# stm32f410rb_pcm5100.net
KiCad netlist of a schematic drawn in EAGLE
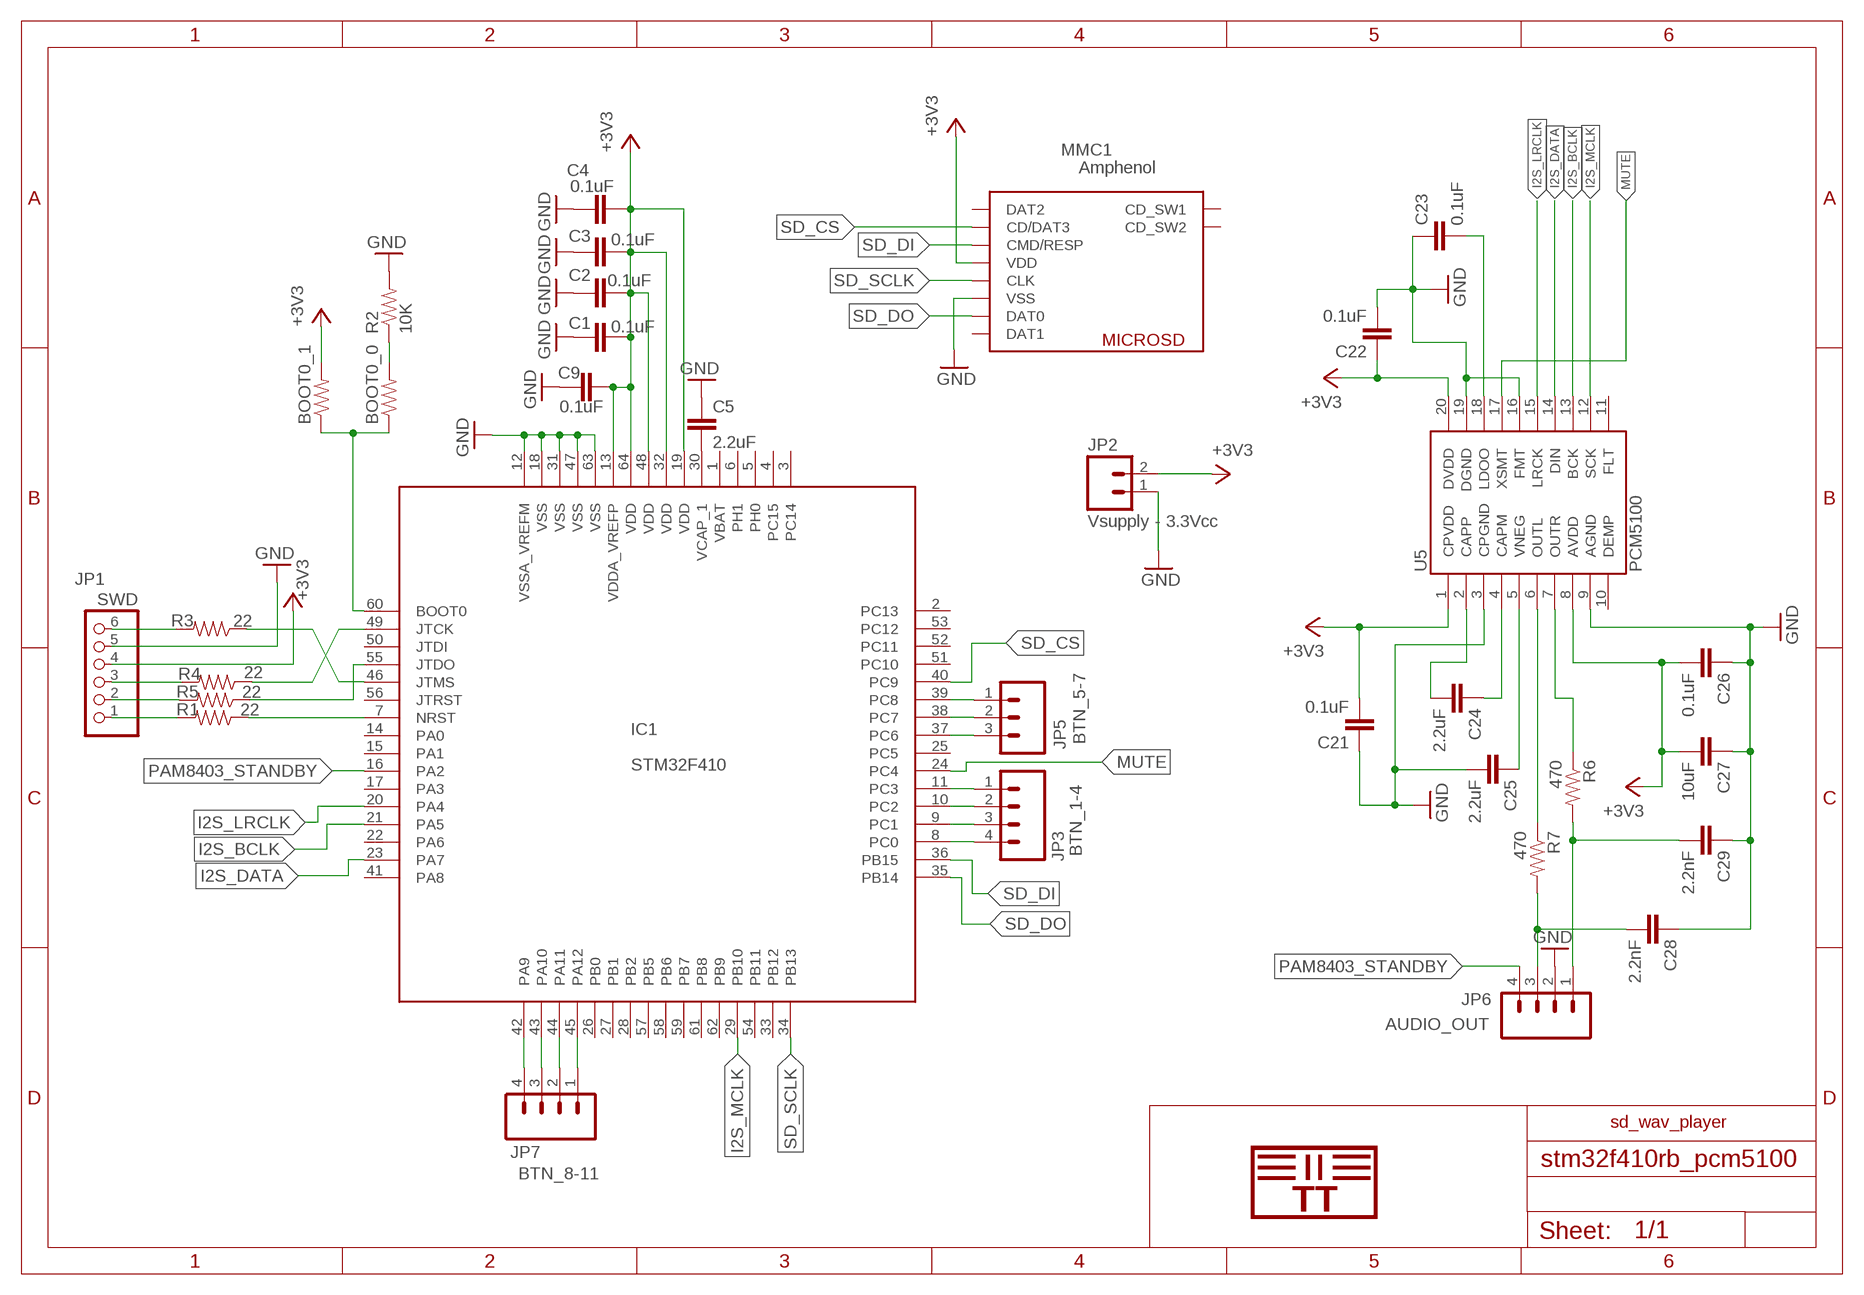
[diagram p0: schematic, sheet 1]

(export (version "E")
  (design (tool "Eeschema 10.0.6"))
  (components
    (comp (ref "BOOT0_0")
      (value "RESISTOR0603-RES")
      (footprint "eagle-import:0603-RES")
      (libsource (lib "eagle-import") (part "RESISTOR0603-RES"))
    )
    (comp (ref "BOOT0_1")
      (value "RESISTOR0603-RES")
      (footprint "eagle-import:0603-RES")
      (libsource (lib "eagle-import") (part "RESISTOR0603-RES"))
    )
    (comp (ref "C1")
      (value "0.1uF")
      (footprint "eagle-import:0805")
      (libsource (lib "eagle-import") (part "CAP0805"))
    )
    (comp (ref "C2")
      (value "0.1uF")
      (footprint "eagle-import:0805")
      (libsource (lib "eagle-import") (part "CAP0805"))
    )
    (comp (ref "C3")
      (value "0.1uF")
      (footprint "eagle-import:0805")
      (libsource (lib "eagle-import") (part "CAP0805"))
    )
    (comp (ref "C4")
      (value "0.1uF")
      (footprint "eagle-import:0805")
      (libsource (lib "eagle-import") (part "CAP0805"))
    )
    (comp (ref "C5")
      (value "2.2uF")
      (footprint "eagle-import:0805")
      (libsource (lib "eagle-import") (part "CAP0805"))
    )
    (comp (ref "C9")
      (value "0.1uF")
      (footprint "eagle-import:0805")
      (libsource (lib "eagle-import") (part "CAP0805"))
    )
    (comp (ref "C21")
      (value "0.1uF")
      (footprint "eagle-import:0805")
      (libsource (lib "eagle-import") (part "CAP0805"))
    )
    (comp (ref "C22")
      (value "0.1uF")
      (footprint "eagle-import:0805")
      (libsource (lib "eagle-import") (part "CAP0805"))
    )
    (comp (ref "C23")
      (value "0.1uF")
      (footprint "eagle-import:0805")
      (libsource (lib "eagle-import") (part "CAP0805"))
    )
    (comp (ref "C24")
      (value "2.2uF")
      (footprint "eagle-import:0805")
      (libsource (lib "eagle-import") (part "CAP0805"))
    )
    (comp (ref "C25")
      (value "2.2uF")
      (footprint "eagle-import:0805")
      (libsource (lib "eagle-import") (part "CAP0805"))
    )
    (comp (ref "C26")
      (value "0.1uF")
      (footprint "eagle-import:0805")
      (libsource (lib "eagle-import") (part "CAP0805"))
    )
    (comp (ref "C27")
      (value "10uF")
      (footprint "eagle-import:0805")
      (libsource (lib "eagle-import") (part "CAP0805"))
    )
    (comp (ref "C28")
      (value "2.2nF")
      (footprint "eagle-import:0805")
      (libsource (lib "eagle-import") (part "CAP0805"))
    )
    (comp (ref "C29")
      (value "2.2nF")
      (footprint "eagle-import:0805")
      (libsource (lib "eagle-import") (part "CAP0805"))
    )
    (comp (ref "IC1")
      (value "STM32F410")
      (footprint "eagle-import:LQFP64")
      (libsource (lib "eagle-import") (part "STM32F410_8_B_LQFP64"))
    )
    (comp (ref "JP1")
      (value "SWD")
      (footprint "eagle-import:1X06")
      (libsource (lib "eagle-import") (part "PINHD-1X6"))
    )
    (comp (ref "JP2")
      (value "Vsupply - 3.3Vcc")
      (footprint "eagle-import:SCREWTERMINAL-3.5MM-2")
      (libsource (lib "eagle-import") (part "M023.5MM"))
    )
    (comp (ref "JP3")
      (value "BTN_1-4")
      (footprint "eagle-import:SCREWTERMINAL-3.5MM-4")
      (libsource (lib "eagle-import") (part "M04SCREW"))
    )
    (comp (ref "JP5")
      (value "BTN_5-7")
      (footprint "eagle-import:SCREWTERMINAL-3.5MM-3")
      (libsource (lib "eagle-import") (part "M03SCREW"))
    )
    (comp (ref "JP6")
      (value "AUDIO_OUT")
      (footprint "eagle-import:SCREWTERMINAL-3.5MM-4")
      (libsource (lib "eagle-import") (part "M04SCREW"))
    )
    (comp (ref "JP7")
      (value "BTN_8-11")
      (footprint "eagle-import:SCREWTERMINAL-3.5MM-4")
      (libsource (lib "eagle-import") (part "M04SCREW"))
    )
    (comp (ref "MMC1")
      (value "Amphenol")
      (footprint "eagle-import:MICROSD_AMPHENOL")
      (libsource (lib "eagle-import") (part "MICROSD_AMPHENOL"))
    )
    (comp (ref "R1")
      (value "22")
      (footprint "eagle-import:0805")
      (libsource (lib "eagle-import") (part "RESISTOR0805-RES"))
    )
    (comp (ref "R2")
      (value "10K")
      (footprint "eagle-import:0805")
      (libsource (lib "eagle-import") (part "RESISTOR0805-RES"))
    )
    (comp (ref "R3")
      (value "22")
      (footprint "eagle-import:0805")
      (libsource (lib "eagle-import") (part "RESISTOR0805-RES"))
    )
    (comp (ref "R4")
      (value "22")
      (footprint "eagle-import:0805")
      (libsource (lib "eagle-import") (part "RESISTOR0805-RES"))
    )
    (comp (ref "R5")
      (value "22")
      (footprint "eagle-import:0805")
      (libsource (lib "eagle-import") (part "RESISTOR0805-RES"))
    )
    (comp (ref "R6")
      (value "470")
      (footprint "eagle-import:0805")
      (libsource (lib "eagle-import") (part "RESISTOR0805-RES"))
    )
    (comp (ref "R7")
      (value "470")
      (footprint "eagle-import:0805")
      (libsource (lib "eagle-import") (part "RESISTOR0805-RES"))
    )
    (comp (ref "U5")
      (value "PCM5100")
      (footprint "eagle-import:ROBERTSONICS_PW_R-PDSO-G20")
      (libsource (lib "eagle-import") (part "ROBERTSONICS_PCM5100"))
    )
  )
  (nets
    (net (code "1") (name "+3V3") (class "Default")
      (node (ref "BOOT0_1") (pin "2") (pinfunction "2_2") (pintype "passive"))
      (node (ref "C1") (pin "1") (pinfunction "1_1") (pintype "passive"))
      (node (ref "C2") (pin "1") (pinfunction "1_1") (pintype "passive"))
      (node (ref "C21") (pin "2") (pinfunction "2_2") (pintype "passive"))
      (node (ref "C22") (pin "1") (pinfunction "1_1") (pintype "passive"))
      (node (ref "C26") (pin "2") (pinfunction "2_2") (pintype "passive"))
      (node (ref "C27") (pin "2") (pinfunction "2_2") (pintype "passive"))
      (node (ref "C3") (pin "1") (pinfunction "1_1") (pintype "passive"))
      (node (ref "C4") (pin "1") (pinfunction "1_1") (pintype "passive"))
      (node (ref "C9") (pin "1") (pinfunction "1_1") (pintype "passive"))
      (node (ref "IC1") (pin "13") (pinfunction "VDDA_VREFP_13") (pintype "power_in"))
      (node (ref "IC1") (pin "19") (pinfunction "VDD_19") (pintype "power_in"))
      (node (ref "IC1") (pin "32") (pinfunction "VDD_32") (pintype "power_in"))
      (node (ref "IC1") (pin "48") (pinfunction "VDD_48") (pintype "power_in"))
      (node (ref "IC1") (pin "64") (pinfunction "VDD_64") (pintype "power_in"))
      (node (ref "JP1") (pin "4") (pinfunction "4_4") (pintype "passive"))
      (node (ref "JP2") (pin "2") (pinfunction "2_2") (pintype "passive"))
      (node (ref "MMC1") (pin "VDD") (pinfunction "VDD_VDD") (pintype "bidirectional"))
      (node (ref "U5") (pin "1") (pinfunction "CPVDD_1") (pintype "bidirectional"))
      (node (ref "U5") (pin "20") (pinfunction "DVDD_20") (pintype "bidirectional"))
      (node (ref "U5") (pin "8") (pinfunction "AVDD_8") (pintype "bidirectional"))
    )
    (net (code "2") (name "GND") (class "Default")
      (node (ref "C1") (pin "2") (pinfunction "2_2") (pintype "passive"))
      (node (ref "C2") (pin "2") (pinfunction "2_2") (pintype "passive"))
      (node (ref "C21") (pin "1") (pinfunction "1_1") (pintype "passive"))
      (node (ref "C22") (pin "2") (pinfunction "2_2") (pintype "passive"))
      (node (ref "C23") (pin "1") (pinfunction "1_1") (pintype "passive"))
      (node (ref "C25") (pin "2") (pinfunction "2_2") (pintype "passive"))
      (node (ref "C26") (pin "1") (pinfunction "1_1") (pintype "passive"))
      (node (ref "C27") (pin "1") (pinfunction "1_1") (pintype "passive"))
      (node (ref "C28") (pin "1") (pinfunction "1_1") (pintype "passive"))
      (node (ref "C29") (pin "1") (pinfunction "1_1") (pintype "passive"))
      (node (ref "C3") (pin "2") (pinfunction "2_2") (pintype "passive"))
      (node (ref "C4") (pin "2") (pinfunction "2_2") (pintype "passive"))
      (node (ref "C5") (pin "1") (pinfunction "1_1") (pintype "passive"))
      (node (ref "C9") (pin "2") (pinfunction "2_2") (pintype "passive"))
      (node (ref "IC1") (pin "12") (pinfunction "VSSA_VREFM_12") (pintype "power_in"))
      (node (ref "IC1") (pin "18") (pinfunction "VSS_18") (pintype "power_in"))
      (node (ref "IC1") (pin "31") (pinfunction "VSS_31") (pintype "power_in"))
      (node (ref "IC1") (pin "47") (pinfunction "VSS_47") (pintype "power_in"))
      (node (ref "IC1") (pin "63") (pinfunction "VSS_63") (pintype "power_in"))
      (node (ref "JP1") (pin "5") (pinfunction "5_5") (pintype "passive"))
      (node (ref "JP2") (pin "1") (pinfunction "1_1") (pintype "passive"))
      (node (ref "JP6") (pin "2") (pinfunction "2_2") (pintype "passive"))
      (node (ref "MMC1") (pin "VSS") (pinfunction "VSS_VSS") (pintype "bidirectional"))
      (node (ref "R2") (pin "2") (pinfunction "2_2") (pintype "passive"))
      (node (ref "U5") (pin "16") (pinfunction "FMT_16") (pintype "bidirectional"))
      (node (ref "U5") (pin "19") (pinfunction "DGND_19") (pintype "bidirectional"))
      (node (ref "U5") (pin "3") (pinfunction "CPGND_3") (pintype "bidirectional"))
      (node (ref "U5") (pin "9") (pinfunction "AGND_9") (pintype "bidirectional"))
    )
    (net (code "3") (name "I2S_BCLK") (class "Default")
      (node (ref "IC1") (pin "21") (pinfunction "PA5_21") (pintype "bidirectional"))
      (node (ref "U5") (pin "13") (pinfunction "BCK_13") (pintype "bidirectional"))
    )
    (net (code "4") (name "I2S_DATA") (class "Default")
      (node (ref "IC1") (pin "23") (pinfunction "PA7_23") (pintype "bidirectional"))
      (node (ref "U5") (pin "14") (pinfunction "DIN_14") (pintype "bidirectional"))
    )
    (net (code "5") (name "I2S_LRCLK") (class "Default")
      (node (ref "IC1") (pin "20") (pinfunction "PA4_20") (pintype "bidirectional"))
      (node (ref "U5") (pin "15") (pinfunction "LRCK_15") (pintype "bidirectional"))
    )
    (net (code "6") (name "I2S_MCLK") (class "Default")
      (node (ref "IC1") (pin "29") (pinfunction "PB10_29") (pintype "bidirectional"))
      (node (ref "U5") (pin "12") (pinfunction "SCK_12") (pintype "bidirectional"))
    )
    (net (code "7") (name "MUTE") (class "Default")
      (node (ref "IC1") (pin "24") (pinfunction "PC4_24") (pintype "bidirectional"))
      (node (ref "U5") (pin "17") (pinfunction "XSMT_17") (pintype "bidirectional"))
    )
    (net (code "8") (name "Net-(BOOT0_0-Pad2)") (class "Default")
      (node (ref "BOOT0_0") (pin "2") (pinfunction "2_2") (pintype "passive"))
      (node (ref "R2") (pin "1") (pinfunction "1_1") (pintype "passive"))
    )
    (net (code "9") (name "Net-(C28-Pad2)") (class "Default")
      (node (ref "C28") (pin "2") (pinfunction "2_2") (pintype "passive"))
      (node (ref "JP6") (pin "3") (pinfunction "3_3") (pintype "passive"))
      (node (ref "R7") (pin "2") (pinfunction "2_2") (pintype "passive"))
    )
    (net (code "10") (name "Net-(C29-Pad2)") (class "Default")
      (node (ref "C29") (pin "2") (pinfunction "2_2") (pintype "passive"))
      (node (ref "JP6") (pin "1") (pinfunction "1_1") (pintype "passive"))
      (node (ref "R6") (pin "2") (pinfunction "2_2") (pintype "passive"))
    )
    (net (code "11") (name "Net-(IC1-BOOT0)") (class "Default")
      (node (ref "BOOT0_0") (pin "1") (pinfunction "1_1") (pintype "passive"))
      (node (ref "BOOT0_1") (pin "1") (pinfunction "1_1") (pintype "passive"))
      (node (ref "IC1") (pin "60") (pinfunction "BOOT0_60") (pintype "input"))
    )
    (net (code "12") (name "Net-(IC1-JTCK)") (class "Default")
      (node (ref "IC1") (pin "49") (pinfunction "JTCK_49") (pintype "input"))
      (node (ref "R4") (pin "1") (pinfunction "1_1") (pintype "passive"))
    )
    (net (code "13") (name "Net-(IC1-JTDO)") (class "Default")
      (node (ref "IC1") (pin "55") (pinfunction "JTDO_55") (pintype "output"))
      (node (ref "R5") (pin "1") (pinfunction "1_1") (pintype "passive"))
    )
    (net (code "14") (name "Net-(IC1-JTMS)") (class "Default")
      (node (ref "IC1") (pin "46") (pinfunction "JTMS_46") (pintype "input"))
      (node (ref "R3") (pin "1") (pinfunction "1_1") (pintype "passive"))
    )
    (net (code "15") (name "Net-(IC1-NRST)") (class "Default")
      (node (ref "IC1") (pin "7") (pinfunction "NRST_7") (pintype "input"))
      (node (ref "R1") (pin "1") (pinfunction "1_1") (pintype "passive"))
    )
    (net (code "16") (name "Net-(IC1-PA9)") (class "Default")
      (node (ref "IC1") (pin "42") (pinfunction "PA9_42") (pintype "bidirectional"))
      (node (ref "JP7") (pin "4") (pinfunction "4_4") (pintype "passive"))
    )
    (net (code "17") (name "Net-(IC1-PA10)") (class "Default")
      (node (ref "IC1") (pin "43") (pinfunction "PA10_43") (pintype "bidirectional"))
      (node (ref "JP7") (pin "3") (pinfunction "3_3") (pintype "passive"))
    )
    (net (code "18") (name "Net-(IC1-PA11)") (class "Default")
      (node (ref "IC1") (pin "44") (pinfunction "PA11_44") (pintype "bidirectional"))
      (node (ref "JP7") (pin "2") (pinfunction "2_2") (pintype "passive"))
    )
    (net (code "19") (name "Net-(IC1-PA12)") (class "Default")
      (node (ref "IC1") (pin "45") (pinfunction "PA12_45") (pintype "bidirectional"))
      (node (ref "JP7") (pin "1") (pinfunction "1_1") (pintype "passive"))
    )
    (net (code "20") (name "Net-(IC1-PC0)") (class "Default")
      (node (ref "IC1") (pin "8") (pinfunction "PC0_8") (pintype "bidirectional"))
      (node (ref "JP3") (pin "4") (pinfunction "4_4") (pintype "passive"))
    )
    (net (code "21") (name "Net-(IC1-PC1)") (class "Default")
      (node (ref "IC1") (pin "9") (pinfunction "PC1_9") (pintype "bidirectional"))
      (node (ref "JP3") (pin "3") (pinfunction "3_3") (pintype "passive"))
    )
    (net (code "22") (name "Net-(IC1-PC2)") (class "Default")
      (node (ref "IC1") (pin "10") (pinfunction "PC2_10") (pintype "bidirectional"))
      (node (ref "JP3") (pin "2") (pinfunction "2_2") (pintype "passive"))
    )
    (net (code "23") (name "Net-(IC1-PC3)") (class "Default")
      (node (ref "IC1") (pin "11") (pinfunction "PC3_11") (pintype "bidirectional"))
      (node (ref "JP3") (pin "1") (pinfunction "1_1") (pintype "passive"))
    )
    (net (code "24") (name "Net-(IC1-PC6)") (class "Default")
      (node (ref "IC1") (pin "37") (pinfunction "PC6_37") (pintype "bidirectional"))
      (node (ref "JP5") (pin "3") (pinfunction "3_3") (pintype "passive"))
    )
    (net (code "25") (name "Net-(IC1-PC7)") (class "Default")
      (node (ref "IC1") (pin "38") (pinfunction "PC7_38") (pintype "bidirectional"))
      (node (ref "JP5") (pin "2") (pinfunction "2_2") (pintype "passive"))
    )
    (net (code "26") (name "Net-(IC1-PC8)") (class "Default")
      (node (ref "IC1") (pin "39") (pinfunction "PC8_39") (pintype "bidirectional"))
      (node (ref "JP5") (pin "1") (pinfunction "1_1") (pintype "passive"))
    )
    (net (code "27") (name "Net-(IC1-VCAP_1)") (class "Default")
      (node (ref "C5") (pin "2") (pinfunction "2_2") (pintype "passive"))
      (node (ref "IC1") (pin "30") (pinfunction "VCAP_1_30") (pintype "passive"))
    )
    (net (code "28") (name "Net-(JP1-Pad1)") (class "Default")
      (node (ref "JP1") (pin "1") (pinfunction "1_1") (pintype "passive"))
      (node (ref "R1") (pin "2") (pinfunction "2_2") (pintype "passive"))
    )
    (net (code "29") (name "Net-(JP1-Pad2)") (class "Default")
      (node (ref "JP1") (pin "2") (pinfunction "2_2") (pintype "passive"))
      (node (ref "R5") (pin "2") (pinfunction "2_2") (pintype "passive"))
    )
    (net (code "30") (name "Net-(JP1-Pad3)") (class "Default")
      (node (ref "JP1") (pin "3") (pinfunction "3_3") (pintype "passive"))
      (node (ref "R4") (pin "2") (pinfunction "2_2") (pintype "passive"))
    )
    (net (code "31") (name "Net-(JP1-Pad6)") (class "Default")
      (node (ref "JP1") (pin "6") (pinfunction "6_6") (pintype "passive"))
      (node (ref "R3") (pin "2") (pinfunction "2_2") (pintype "passive"))
    )
    (net (code "32") (name "Net-(U5-CAPM)") (class "Default")
      (node (ref "C24") (pin "1") (pinfunction "1_1") (pintype "passive"))
      (node (ref "U5") (pin "4") (pinfunction "CAPM_4") (pintype "bidirectional"))
    )
    (net (code "33") (name "Net-(U5-CAPP)") (class "Default")
      (node (ref "C24") (pin "2") (pinfunction "2_2") (pintype "passive"))
      (node (ref "U5") (pin "2") (pinfunction "CAPP_2") (pintype "bidirectional"))
    )
    (net (code "34") (name "Net-(U5-LDOO)") (class "Default")
      (node (ref "C23") (pin "2") (pinfunction "2_2") (pintype "passive"))
      (node (ref "U5") (pin "18") (pinfunction "LDOO_18") (pintype "bidirectional"))
    )
    (net (code "35") (name "Net-(U5-OUTL)") (class "Default")
      (node (ref "R7") (pin "1") (pinfunction "1_1") (pintype "passive"))
      (node (ref "U5") (pin "6") (pinfunction "OUTL_6") (pintype "bidirectional"))
    )
    (net (code "36") (name "Net-(U5-OUTR)") (class "Default")
      (node (ref "R6") (pin "1") (pinfunction "1_1") (pintype "passive"))
      (node (ref "U5") (pin "7") (pinfunction "OUTR_7") (pintype "bidirectional"))
    )
    (net (code "37") (name "Net-(U5-VNEG)") (class "Default")
      (node (ref "C25") (pin "1") (pinfunction "1_1") (pintype "passive"))
      (node (ref "U5") (pin "5") (pinfunction "VNEG_5") (pintype "bidirectional"))
    )
    (net (code "38") (name "PAM8403_STANDBY") (class "Default")
      (node (ref "IC1") (pin "16") (pinfunction "PA2_16") (pintype "bidirectional"))
      (node (ref "JP6") (pin "4") (pinfunction "4_4") (pintype "passive"))
    )
    (net (code "39") (name "SD_CS") (class "Default")
      (node (ref "IC1") (pin "40") (pinfunction "PC9_40") (pintype "bidirectional"))
      (node (ref "MMC1") (pin "CD/DAT3") (pinfunction "CD/DAT3_CD/DAT3") (pintype "bidirectional"))
    )
    (net (code "40") (name "SD_DI") (class "Default")
      (node (ref "IC1") (pin "36") (pinfunction "PB15_36") (pintype "bidirectional"))
      (node (ref "MMC1") (pin "CMD/RESP") (pinfunction "CMD/RESP_CMD/RESP") (pintype "bidirectional"))
    )
    (net (code "41") (name "SD_DO") (class "Default")
      (node (ref "IC1") (pin "35") (pinfunction "PB14_35") (pintype "bidirectional"))
      (node (ref "MMC1") (pin "DAT0") (pinfunction "DAT0_DAT0") (pintype "bidirectional"))
    )
    (net (code "42") (name "SD_SCLK") (class "Default")
      (node (ref "IC1") (pin "34") (pinfunction "PB13_34") (pintype "bidirectional"))
      (node (ref "MMC1") (pin "CLK") (pinfunction "CLK_CLK") (pintype "bidirectional"))
    )
    (net (code "43") (name "unconnected-(IC1-JTDI-Pad50)") (class "Default")
      (node (ref "IC1") (pin "50") (pinfunction "JTDI_50") (pintype "input"))
    )
    (net (code "44") (name "unconnected-(IC1-JTRST-Pad56)") (class "Default")
      (node (ref "IC1") (pin "56") (pinfunction "JTRST_56") (pintype "input"))
    )
    (net (code "45") (name "unconnected-(IC1-PA0-Pad14)") (class "Default")
      (node (ref "IC1") (pin "14") (pinfunction "PA0_14") (pintype "bidirectional"))
    )
    (net (code "46") (name "unconnected-(IC1-PA1-Pad15)") (class "Default")
      (node (ref "IC1") (pin "15") (pinfunction "PA1_15") (pintype "bidirectional"))
    )
    (net (code "47") (name "unconnected-(IC1-PA3-Pad17)") (class "Default")
      (node (ref "IC1") (pin "17") (pinfunction "PA3_17") (pintype "bidirectional"))
    )
    (net (code "48") (name "unconnected-(IC1-PA6-Pad22)") (class "Default")
      (node (ref "IC1") (pin "22") (pinfunction "PA6_22") (pintype "bidirectional"))
    )
    (net (code "49") (name "unconnected-(IC1-PA8-Pad41)") (class "Default")
      (node (ref "IC1") (pin "41") (pinfunction "PA8_41") (pintype "bidirectional"))
    )
    (net (code "50") (name "unconnected-(IC1-PB0-Pad26)") (class "Default")
      (node (ref "IC1") (pin "26") (pinfunction "PB0_26") (pintype "bidirectional"))
    )
    (net (code "51") (name "unconnected-(IC1-PB1-Pad27)") (class "Default")
      (node (ref "IC1") (pin "27") (pinfunction "PB1_27") (pintype "bidirectional"))
    )
    (net (code "52") (name "unconnected-(IC1-PB2-Pad28)") (class "Default")
      (node (ref "IC1") (pin "28") (pinfunction "PB2_28") (pintype "bidirectional"))
    )
    (net (code "53") (name "unconnected-(IC1-PB5-Pad57)") (class "Default")
      (node (ref "IC1") (pin "57") (pinfunction "PB5_57") (pintype "bidirectional"))
    )
    (net (code "54") (name "unconnected-(IC1-PB6-Pad58)") (class "Default")
      (node (ref "IC1") (pin "58") (pinfunction "PB6_58") (pintype "bidirectional"))
    )
    (net (code "55") (name "unconnected-(IC1-PB7-Pad59)") (class "Default")
      (node (ref "IC1") (pin "59") (pinfunction "PB7_59") (pintype "bidirectional"))
    )
    (net (code "56") (name "unconnected-(IC1-PB8-Pad61)") (class "Default")
      (node (ref "IC1") (pin "61") (pinfunction "PB8_61") (pintype "bidirectional"))
    )
    (net (code "57") (name "unconnected-(IC1-PB9-Pad62)") (class "Default")
      (node (ref "IC1") (pin "62") (pinfunction "PB9_62") (pintype "bidirectional"))
    )
    (net (code "58") (name "unconnected-(IC1-PB11-Pad54)") (class "Default")
      (node (ref "IC1") (pin "54") (pinfunction "PB11_54") (pintype "bidirectional"))
    )
    (net (code "59") (name "unconnected-(IC1-PB12-Pad33)") (class "Default")
      (node (ref "IC1") (pin "33") (pinfunction "PB12_33") (pintype "bidirectional"))
    )
    (net (code "60") (name "unconnected-(IC1-PC5-Pad25)") (class "Default")
      (node (ref "IC1") (pin "25") (pinfunction "PC5_25") (pintype "bidirectional"))
    )
    (net (code "61") (name "unconnected-(IC1-PC10-Pad51)") (class "Default")
      (node (ref "IC1") (pin "51") (pinfunction "PC10_51") (pintype "bidirectional"))
    )
    (net (code "62") (name "unconnected-(IC1-PC11-Pad52)") (class "Default")
      (node (ref "IC1") (pin "52") (pinfunction "PC11_52") (pintype "bidirectional"))
    )
    (net (code "63") (name "unconnected-(IC1-PC12-Pad53)") (class "Default")
      (node (ref "IC1") (pin "53") (pinfunction "PC12_53") (pintype "bidirectional"))
    )
    (net (code "64") (name "unconnected-(IC1-PC13-Pad2)") (class "Default")
      (node (ref "IC1") (pin "2") (pinfunction "PC13_2") (pintype "bidirectional"))
    )
    (net (code "65") (name "unconnected-(IC1-PC14-Pad3)") (class "Default")
      (node (ref "IC1") (pin "3") (pinfunction "PC14_3") (pintype "bidirectional"))
    )
    (net (code "66") (name "unconnected-(IC1-PC15-Pad4)") (class "Default")
      (node (ref "IC1") (pin "4") (pinfunction "PC15_4") (pintype "bidirectional"))
    )
    (net (code "67") (name "unconnected-(IC1-PH0-Pad5)") (class "Default")
      (node (ref "IC1") (pin "5") (pinfunction "PH0_5") (pintype "bidirectional"))
    )
    (net (code "68") (name "unconnected-(IC1-PH1-Pad6)") (class "Default")
      (node (ref "IC1") (pin "6") (pinfunction "PH1_6") (pintype "bidirectional"))
    )
    (net (code "69") (name "unconnected-(IC1-VBAT-Pad1)") (class "Default")
      (node (ref "IC1") (pin "1") (pinfunction "VBAT_1") (pintype "passive"))
    )
    (net (code "70") (name "unconnected-(MMC1-PadCD_SW1)") (class "Default")
      (node (ref "MMC1") (pin "CD_SW1") (pinfunction "CD_SW1_CD_SW1") (pintype "bidirectional"))
    )
    (net (code "71") (name "unconnected-(MMC1-PadCD_SW2)") (class "Default")
      (node (ref "MMC1") (pin "CD_SW2") (pinfunction "CD_SW2_CD_SW2") (pintype "bidirectional"))
    )
    (net (code "72") (name "unconnected-(MMC1-PadDAT1)") (class "Default")
      (node (ref "MMC1") (pin "DAT1") (pinfunction "DAT1_DAT1") (pintype "bidirectional"))
    )
    (net (code "73") (name "unconnected-(MMC1-PadDAT2)") (class "Default")
      (node (ref "MMC1") (pin "DAT2") (pinfunction "DAT2_DAT2") (pintype "bidirectional"))
    )
    (net (code "74") (name "unconnected-(U5-DEMP-Pad10)") (class "Default")
      (node (ref "U5") (pin "10") (pinfunction "DEMP_10") (pintype "bidirectional"))
    )
    (net (code "75") (name "unconnected-(U5-FLT-Pad11)") (class "Default")
      (node (ref "U5") (pin "11") (pinfunction "FLT_11") (pintype "bidirectional"))
    )
  )
)
